# 535_8POV.net
KiCad netlist of a schematic drawn in Altium Designer
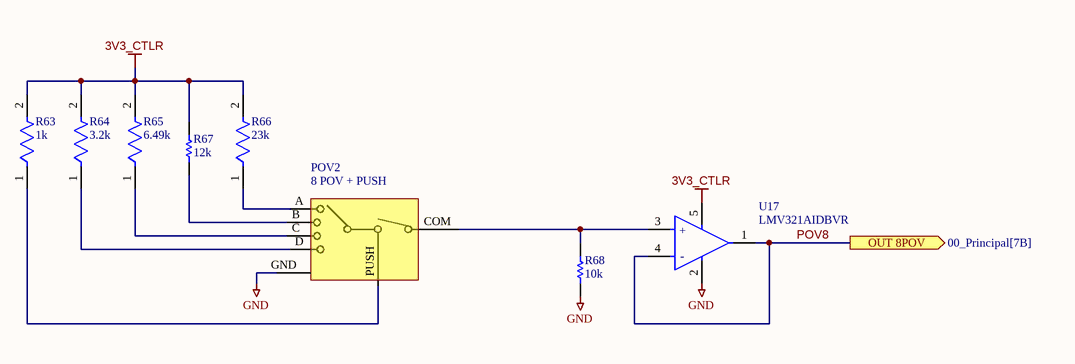
[diagram p0: 535_8POV.SchDoc]

(export (version "E")
  (design (tool "Eeschema 10.0.6"))
  (components
    (comp (ref "POV2")
      (value "8 POV + PUSH")
      (footprint "RKJXM1015004")
      (description "8-directional Stick Switch (with Center-push Function) RKJXM Series")
      (libsource (lib "Esquemas") (part "RKJXM1015004"))
    )
    (comp (ref "R63")
      (value "1k")
      (footprint "FP-MCS0402-IPC_B")
      (description "RES SMD 1.2K OHM 1% 1/10W 0402")
      (fields (field (name "TOLERANCE") "0.1%"))
      (libsource (lib "Altium Content Vault") (part "1029c3af85768c4190bb7ad29bc67b5"))
    )
    (comp (ref "R64")
      (value "3.2k")
      (footprint "FP-RN73R1E-IPC_A")
      (description "3.2kΩ ±0.1% 0.063W, 1/16W Chip Resistor 0402 (1005 Metric) Moisture Resistant Thin Film")
      (libsource (lib "Altium Content Vault") (part "1029c3af85768c4190bb7ad29bc67b5"))
    )
    (comp (ref "R65")
      (value "6.49k")
      (footprint "FP-MCS0402-IPC_A")
      (description "RES SMD 1.2K OHM 1% 1/10W 0402")
      (fields (field (name "TOLERANCE") "1%"))
      (libsource (lib "Altium Content Vault") (part "1029c3af85768c4190bb7ad29bc67b5"))
    )
    (comp (ref "R66")
      (value "23k")
      (footprint "FP-AC0402-MFG")
      (description "RES 23.2kΩ ±1% 0.063W 0402")
      (fields (field (name "TOLERANCE") "1%"))
      (libsource (lib "Altium Content Vault") (part "1029c3af85768c4190bb7ad29bc67b5"))
    )
    (comp (ref "R67")
      (value "12k")
      (footprint "RESC0402(1005)_M")
      (description "12K 0.063W 5% 0402 (1005 Metric)  SMD")
      (fields (field (name "TOLERANCE") "5 %") (field (name "POWER") "0.063 W"))
      (libsource (lib "Altium Content Vault") (part "RES"))
    )
    (comp (ref "R68")
      (value "10k")
      (footprint "RESC1005X40X25ML05T05")
      (fields (field (name "MANUFACTURER") "Panasonic") (field (name "PART NUMBER") "ERJ-2RHD1002X"))
      (libsource (lib "Altium Content Vault") (part "RES"))
    )
    (comp (ref "U17")
      (value "LMV321AIDBVR")
      (footprint "FP-DBV0005A-MFG")
      (description "IC OPAMP GP 1 CIRCUIT SOT23-5")
      (libsource (lib "Altium Content Vault") (part "1dcd28e651784f0a5a8ed6f8452eeff"))
    )
  )
  (nets
    (net (code "1") (name "/POV8") (class "Default")
      (node (ref "U17") (pin "1") (pinfunction "OUT_1") (pintype "passive"))
      (node (ref "U17") (pin "4") (pinfunction "-IN_4") (pintype "tri_state"))
    )
    (net (code "2") (name "3V3_CTLR") (class "Default")
      (node (ref "R63") (pin "2") (pinfunction "2_2") (pintype "passive"))
      (node (ref "R64") (pin "2") (pinfunction "2_2") (pintype "passive"))
      (node (ref "R65") (pin "2") (pinfunction "2_2") (pintype "passive"))
      (node (ref "R66") (pin "2") (pinfunction "2_2") (pintype "passive"))
      (node (ref "R67") (pin "2") (pinfunction "2_2") (pintype "passive"))
      (node (ref "U17") (pin "5") (pinfunction "V+_5") (pintype "passive"))
    )
    (net (code "3") (name "GND") (class "Default")
      (node (ref "POV2") (pin "GND") (pinfunction "GND_GND") (pintype "passive"))
      (node (ref "R68") (pin "1") (pinfunction "1_1") (pintype "passive"))
      (node (ref "U17") (pin "2") (pinfunction "V-_2") (pintype "passive"))
    )
    (net (code "4") (name "Net-(POV2-DIRA)") (class "Default")
      (node (ref "POV2") (pin "A") (pinfunction "DIRA_A") (pintype "passive"))
      (node (ref "R66") (pin "1") (pinfunction "1_1") (pintype "passive"))
    )
    (net (code "5") (name "Net-(POV2-DIRB)") (class "Default")
      (node (ref "POV2") (pin "B") (pinfunction "DIRB_B") (pintype "passive"))
      (node (ref "R67") (pin "1") (pinfunction "1_1") (pintype "passive"))
    )
    (net (code "6") (name "Net-(POV2-DIRC)") (class "Default")
      (node (ref "POV2") (pin "C") (pinfunction "DIRC_C") (pintype "passive"))
      (node (ref "R65") (pin "1") (pinfunction "1_1") (pintype "passive"))
    )
    (net (code "7") (name "Net-(POV2-DIRD)") (class "Default")
      (node (ref "POV2") (pin "D") (pinfunction "DIRD_D") (pintype "passive"))
      (node (ref "R64") (pin "1") (pinfunction "1_1") (pintype "passive"))
    )
    (net (code "8") (name "Net-(POV2-PadPUSH)") (class "Default")
      (node (ref "POV2") (pin "PUSH") (pinfunction "PUSH_PUSH") (pintype "passive"))
      (node (ref "R63") (pin "1") (pinfunction "1_1") (pintype "passive"))
    )
    (net (code "9") (name "Net-(U17-+IN)") (class "Default")
      (node (ref "POV2") (pin "COM") (pinfunction "COM_COM") (pintype "passive"))
      (node (ref "R68") (pin "2") (pinfunction "2_2") (pintype "passive"))
      (node (ref "U17") (pin "3") (pinfunction "+IN_3") (pintype "tri_state"))
    )
  )
)
